# MicroSD.net
KiCad netlist of a schematic drawn in Altium Designer
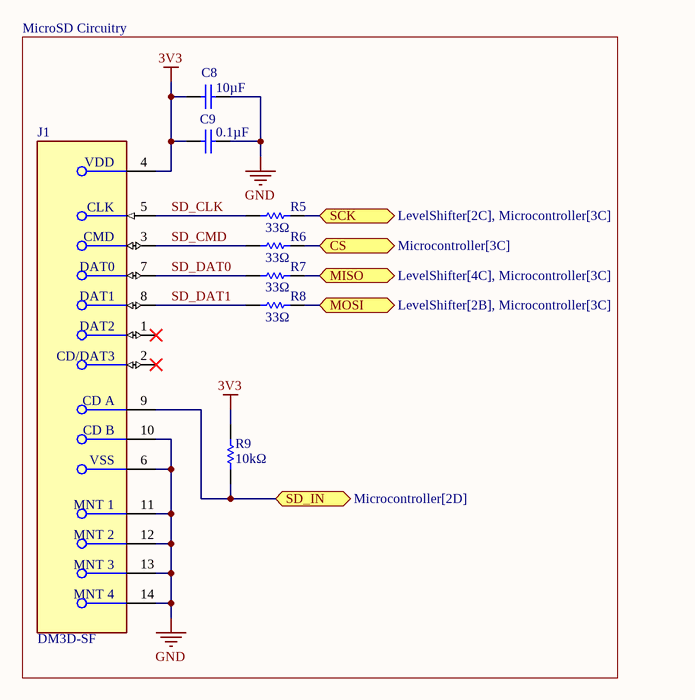
[diagram p0: MicroSD.SchDoc]

(export (version "E")
  (design (tool "Eeschema 10.0.6"))
  (components
    (comp (ref "C8")
      (value "10µF")
      (footprint "CAPC3216X180X50ML20T25")
      (description "CAP, Ceramic, 10 uF, +/- 10%, 16 V, -55 to 125 degC, 1206 (3216 Metric), RoHS, Tape and Reel")
      (fields (field (name "TOLERANCE") "5%"))
      (libsource (lib "") (part "CAP-NP-2_1"))
    )
    (comp (ref "C9")
      (value "0.1µF")
      (footprint "CAPC3216X100X50ML20T25")
      (description "Chip Capacitor, 100 nF, +/- 10%, 25 V, -55 to 125 degC, 1206 (3216 Metric), RoHS, Tape and Reel")
      (fields (field (name "MANUFACTURER") "Kemet"))
      (libsource (lib "Altium Content Vault") (part "CAP-NP-2"))
    )
    (comp (ref "J1")
      (value "DM3D-SF")
      (footprint "FP-DM3D-SF-MFG")
      (description "CONN MICRO SD CARD PUSH-PULL")
      (libsource (lib "Altium Content Vault") (part "375756fe1061de806c40c19e9001ea3"))
    )
    (comp (ref "R5")
      (value "33Ω")
      (footprint "RESC1206(3216)_L")
      (description "33R 0.25W 1% 1206 (3216 Metric)  SMD")
      (fields (field (name "TOLERANCE") "1 %") (field (name "POWER") "0.25 W"))
      (libsource (lib "Altium Content Vault") (part "RES"))
    )
    (comp (ref "R6")
      (value "33Ω")
      (footprint "RESC1206(3216)_L")
      (description "33R 0.25W 1% 1206 (3216 Metric)  SMD")
      (fields (field (name "TOLERANCE") "1 %") (field (name "POWER") "0.25 W"))
      (libsource (lib "Altium Content Vault") (part "RES"))
    )
    (comp (ref "R7")
      (value "33Ω")
      (footprint "RESC1206(3216)_L")
      (description "33R 0.25W 1% 1206 (3216 Metric)  SMD")
      (fields (field (name "TOLERANCE") "1 %") (field (name "POWER") "0.25 W"))
      (libsource (lib "Altium Content Vault") (part "RES"))
    )
    (comp (ref "R8")
      (value "33Ω")
      (footprint "RESC1206(3216)_L")
      (description "33R 0.25W 1% 1206 (3216 Metric)  SMD")
      (fields (field (name "TOLERANCE") "1 %") (field (name "POWER") "0.25 W"))
      (libsource (lib "Altium Content Vault") (part "RES"))
    )
    (comp (ref "R9")
      (value "10kΩ")
      (footprint "RESC3116X65X40LL10T20")
      (description "Chip Resistor, 10 KOhm, +/- 1%, 0.25 W, -55 to 155 degC, 1206 (3216 Metric), RoHS, Tape and Reel")
      (fields (field (name "TOLERANCE") "1%") (field (name "MANUFACTURER") "Yageo"))
      (libsource (lib "Altium Content Vault") (part "RES-2"))
    )
  )
  (nets
    (net (code "1") (name "/CS") (class "Default")
      (node (ref "R6") (pin "2") (pinfunction "2_2") (pintype "passive"))
    )
    (net (code "2") (name "/MISO") (class "Default")
      (node (ref "R7") (pin "2") (pinfunction "2_2") (pintype "passive"))
    )
    (net (code "3") (name "/MOSI") (class "Default")
      (node (ref "R8") (pin "2") (pinfunction "2_2") (pintype "passive"))
    )
    (net (code "4") (name "/SCK") (class "Default")
      (node (ref "R5") (pin "2") (pinfunction "2_2") (pintype "passive"))
    )
    (net (code "5") (name "/SD_CLK") (class "Default")
      (node (ref "J1") (pin "5") (pinfunction "CLK_5") (pintype "input"))
      (node (ref "R5") (pin "1") (pinfunction "1_1") (pintype "passive"))
    )
    (net (code "6") (name "/SD_CMD") (class "Default")
      (node (ref "J1") (pin "3") (pinfunction "CMD_3") (pintype "bidirectional"))
      (node (ref "R6") (pin "1") (pinfunction "1_1") (pintype "passive"))
    )
    (net (code "7") (name "/SD_DAT0") (class "Default")
      (node (ref "J1") (pin "7") (pinfunction "DAT0_7") (pintype "bidirectional"))
      (node (ref "R7") (pin "1") (pinfunction "1_1") (pintype "passive"))
    )
    (net (code "8") (name "/SD_DAT1") (class "Default")
      (node (ref "J1") (pin "8") (pinfunction "DAT1_8") (pintype "bidirectional"))
      (node (ref "R8") (pin "1") (pinfunction "1_1") (pintype "passive"))
    )
    (net (code "9") (name "/SD_IN") (class "Default")
      (node (ref "J1") (pin "9") (pinfunction "CD_A_9") (pintype "passive"))
      (node (ref "R9") (pin "1") (pinfunction "1_1") (pintype "passive"))
    )
    (net (code "10") (name "3V3") (class "Default")
      (node (ref "C8") (pin "2") (pinfunction "2_2") (pintype "passive"))
      (node (ref "C9") (pin "2") (pinfunction "2_2") (pintype "passive"))
      (node (ref "J1") (pin "4") (pinfunction "VDD_4") (pintype "power_in"))
      (node (ref "R9") (pin "2") (pinfunction "2_2") (pintype "passive"))
    )
    (net (code "11") (name "GND") (class "Default")
      (node (ref "C8") (pin "1") (pinfunction "1_1") (pintype "passive"))
      (node (ref "C9") (pin "1") (pinfunction "1_1") (pintype "passive"))
      (node (ref "J1") (pin "10") (pinfunction "CD_B_10") (pintype "passive"))
      (node (ref "J1") (pin "11") (pinfunction "MNT_1_11") (pintype "passive"))
      (node (ref "J1") (pin "12") (pinfunction "MNT_2_12") (pintype "passive"))
      (node (ref "J1") (pin "13") (pinfunction "MNT_3_13") (pintype "passive"))
      (node (ref "J1") (pin "14") (pinfunction "MNT_4_14") (pintype "passive"))
      (node (ref "J1") (pin "6") (pinfunction "VSS_6") (pintype "power_in"))
    )
    (net (code "12") (name "unconnected-(J1-CD{slash}DAT3-Pad2)") (class "Default")
      (node (ref "J1") (pin "2") (pinfunction "CD/DAT3_2") (pintype "bidirectional+no_connect"))
    )
    (net (code "13") (name "unconnected-(J1-DAT2-Pad1)") (class "Default")
      (node (ref "J1") (pin "1") (pinfunction "DAT2_1") (pintype "bidirectional+no_connect"))
    )
  )
)
